# Power.net
KiCad netlist of a schematic drawn in Altium Designer
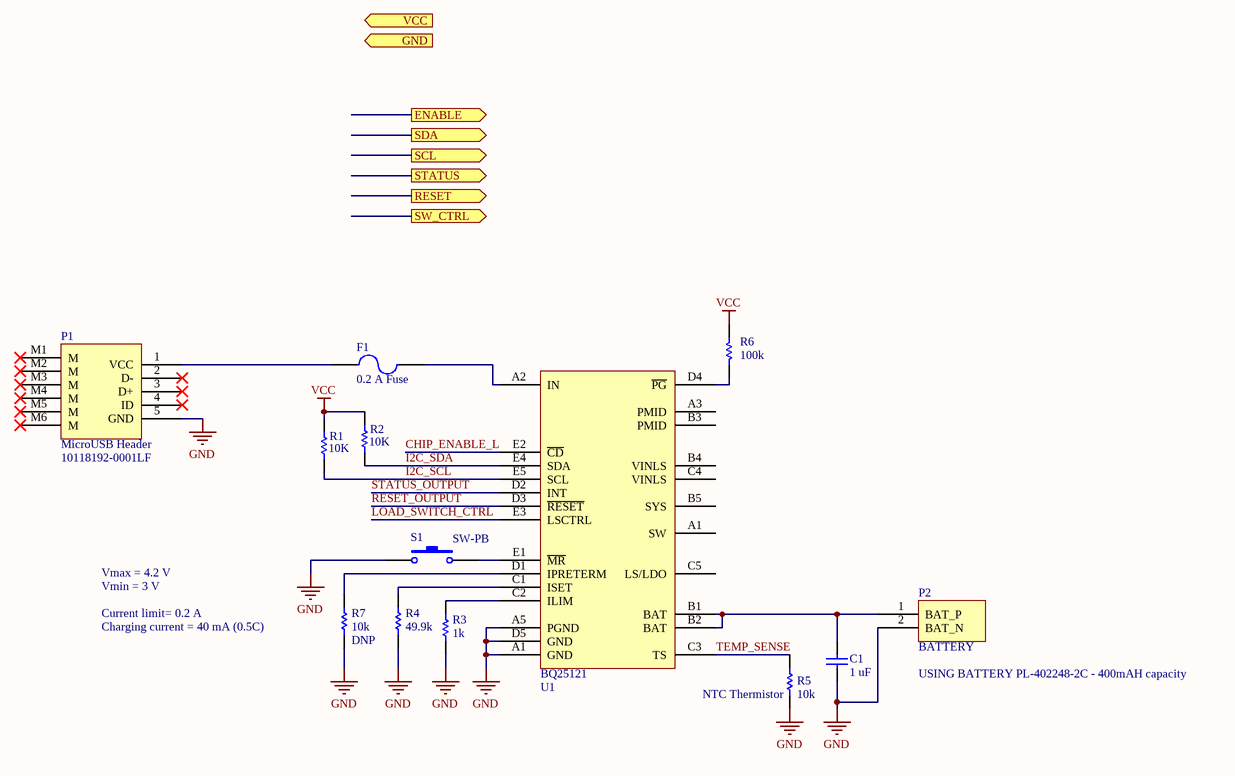
[diagram p0: Power.SchDoc]

(export (version "E")
  (design (tool "Eeschema 10.0.6"))
  (components
    (comp (ref "C1")
      (value "1 uF")
      (footprint "1608[0603]")
      (description "Capacitor")
      (fields (field (name "MANUFACTURER") "Murata") (field (name "Comment") "Cap"))
      (libsource (lib "Miscellaneous Devices") (part "Cap"))
    )
    (comp (ref "F1")
      (value "0.2 A Fuse")
      (footprint "Fuse_0603")
      (description "Fuse")
      (fields (field (name "MANUFACTURER") "AVX"))
      (libsource (lib "Miscellaneous Devices") (part "Fuse 2"))
    )
    (comp (ref "P1")
      (value "MicroUSB Header")
      (footprint "Micro USB B")
      (fields (field (name "MANUFACTURER") "Amphenol FCI") (field (name "MANUFACTURER PN") "10118192-0001LF"))
      (libsource (lib "Chirpwear") (part "Microusb"))
    )
    (comp (ref "P2") (value "BATTERY") (libsource (lib "Chirpwear") (part "BATTERY")))
    (comp (ref "R1")
      (value "10K")
      (footprint "RES0603")
      (description "Resistor")
      (fields (field (name "Comment") "Res1"))
      (libsource (lib "Miscellaneous Devices") (part "Res1"))
    )
    (comp (ref "R2")
      (value "10K")
      (footprint "RES0603")
      (description "Resistor")
      (fields (field (name "Comment") "Res1"))
      (libsource (lib "Miscellaneous Devices") (part "Res1"))
    )
    (comp (ref "R3")
      (value "1k")
      (footprint "RES0603")
      (description "Resistor")
      (fields (field (name "MANUFACTURER") "Yageo") (field (name "TOLERANCE") "1%"))
      (libsource (lib "Miscellaneous Devices") (part "Res1"))
    )
    (comp (ref "R4")
      (value "49.9k")
      (footprint "RES0603")
      (description "Resistor")
      (fields (field (name "MANUFACTURER") "Yageo") (field (name "TOLERANCE") "1%"))
      (libsource (lib "Miscellaneous Devices") (part "Res1"))
    )
    (comp (ref "R5")
      (value "10k")
      (footprint "AXIAL-0.3")
      (description "Resistor")
      (fields (field (name "Comment") "Res1"))
      (libsource (lib "Miscellaneous Devices") (part "Res1"))
    )
    (comp (ref "R6")
      (value "100k")
      (footprint "RES0603")
      (description "Resistor")
      (fields (field (name "MANUFACTURER") "Yageo") (field (name "TOLERANCE") "1%"))
      (libsource (lib "Miscellaneous Devices") (part "Res1"))
    )
    (comp (ref "R7")
      (value "10k")
      (footprint "AXIAL-0.3")
      (description "Resistor")
      (fields (field (name "NO_STUFF") "DNP") (field (name "Comment") "Res1"))
      (libsource (lib "Miscellaneous Devices") (part "Res1"))
    )
    (comp (ref "S1")
      (value "SW-PB")
      (footprint "SPST-2")
      (description "Switch")
      (fields (field (name "PUBLISHER") "Altium Limited"))
      (libsource (lib "Miscellaneous Devices") (part "SW-PB"))
    )
    (comp (ref "U1")
      (value "BQ25121")
      (description "IC BATT CHG LI-ION 25DSBGA")
      (fields (field (name "MANUFACTURER") "TI"))
      (libsource (lib "Chirpwear") (part "BQ2512X"))
    )
  )
  (nets
    (net (code "1") (name "/CHIP_ENABLE_L") (class "Default")
      (node (ref "U1") (pin "E2") (pinfunction "~{CD}_E2") (pintype "passive"))
    )
    (net (code "3") (name "/I2C_SCL") (class "Default")
      (node (ref "R1") (pin "1") (pinfunction "1_1") (pintype "passive"))
      (node (ref "U1") (pin "E5") (pinfunction "SCL_E5") (pintype "passive"))
    )
    (net (code "4") (name "/I2C_SDA") (class "Default")
      (node (ref "R2") (pin "1") (pinfunction "1_1") (pintype "passive"))
      (node (ref "U1") (pin "E4") (pinfunction "SDA_E4") (pintype "passive"))
    )
    (net (code "5") (name "/LOAD_SWITCH_CTRL") (class "Default")
      (node (ref "U1") (pin "E3") (pinfunction "LSCTRL_E3") (pintype "passive"))
    )
    (net (code "7") (name "/RESET_OUTPUT") (class "Default")
      (node (ref "U1") (pin "D3") (pinfunction "~{RESET}_D3") (pintype "passive"))
    )
    (net (code "11") (name "/STATUS_OUTPUT") (class "Default")
      (node (ref "U1") (pin "D2") (pinfunction "INT_D2") (pintype "passive"))
    )
    (net (code "13") (name "/TEMP_SENSE") (class "Default")
      (node (ref "R5") (pin "2") (pinfunction "2_2") (pintype "passive"))
      (node (ref "U1") (pin "C3") (pinfunction "TS_C3") (pintype "passive"))
    )
    (net (code "14") (name "GND") (class "Default")
      (node (ref "C1") (pin "1") (pinfunction "1_1") (pintype "passive"))
      (node (ref "P1") (pin "5") (pinfunction "GND_5") (pintype "passive"))
      (node (ref "P2") (pin "2") (pinfunction "BAT_N_2") (pintype "passive"))
      (node (ref "R3") (pin "1") (pinfunction "1_1") (pintype "passive"))
      (node (ref "R4") (pin "1") (pinfunction "1_1") (pintype "passive"))
      (node (ref "R5") (pin "1") (pinfunction "1_1") (pintype "passive"))
      (node (ref "R7") (pin "1") (pinfunction "1_1") (pintype "passive"))
      (node (ref "S1") (pin "1") (pinfunction "1_1") (pintype "passive"))
      (node (ref "U1") (pin "A1") (pinfunction "GND_A1") (pintype "passive"))
      (node (ref "U1") (pin "A5") (pinfunction "PGND_A5") (pintype "passive"))
      (node (ref "U1") (pin "D5") (pinfunction "GND_D5") (pintype "passive"))
    )
    (net (code "15") (name "Net-(P1-VCC)") (class "Default")
      (node (ref "F1") (pin "1") (pinfunction "1_1") (pintype "passive"))
      (node (ref "P1") (pin "1") (pinfunction "VCC_1") (pintype "passive"))
    )
    (net (code "16") (name "Net-(P2-BAT_P)") (class "Default")
      (node (ref "C1") (pin "2") (pinfunction "2_2") (pintype "passive"))
      (node (ref "P2") (pin "1") (pinfunction "BAT_P_1") (pintype "passive"))
      (node (ref "U1") (pin "B1") (pinfunction "BAT_B1") (pintype "passive"))
      (node (ref "U1") (pin "B2") (pinfunction "BAT_B2") (pintype "passive"))
    )
    (net (code "17") (name "Net-(U1-ILIM)") (class "Default")
      (node (ref "R3") (pin "2") (pinfunction "2_2") (pintype "passive"))
      (node (ref "U1") (pin "C2") (pinfunction "ILIM_C2") (pintype "passive"))
    )
    (net (code "18") (name "Net-(U1-IN)") (class "Default")
      (node (ref "F1") (pin "2") (pinfunction "2_2") (pintype "passive"))
      (node (ref "U1") (pin "A2") (pinfunction "IN_A2") (pintype "passive"))
    )
    (net (code "19") (name "Net-(U1-IPRETERM)") (class "Default")
      (node (ref "R7") (pin "2") (pinfunction "2_2") (pintype "passive"))
      (node (ref "U1") (pin "D1") (pinfunction "IPRETERM_D1") (pintype "passive"))
    )
    (net (code "20") (name "Net-(U1-ISET)") (class "Default")
      (node (ref "R4") (pin "2") (pinfunction "2_2") (pintype "passive"))
      (node (ref "U1") (pin "C1") (pinfunction "ISET_C1") (pintype "passive"))
    )
    (net (code "21") (name "Net-(U1-~{MR})") (class "Default")
      (node (ref "S1") (pin "2") (pinfunction "2_2") (pintype "passive"))
      (node (ref "U1") (pin "E1") (pinfunction "~{MR}_E1") (pintype "passive"))
    )
    (net (code "22") (name "Net-(U1-~{PG})") (class "Default")
      (node (ref "R6") (pin "1") (pinfunction "1_1") (pintype "passive"))
      (node (ref "U1") (pin "D4") (pinfunction "~{PG}_D4") (pintype "passive"))
    )
    (net (code "23") (name "VCC") (class "Default")
      (node (ref "R1") (pin "2") (pinfunction "2_2") (pintype "passive"))
      (node (ref "R2") (pin "2") (pinfunction "2_2") (pintype "passive"))
      (node (ref "R6") (pin "2") (pinfunction "2_2") (pintype "passive"))
    )
    (net (code "24") (name "unconnected-(P1-D+-Pad3)") (class "Default")
      (node (ref "P1") (pin "3") (pinfunction "D+_3") (pintype "passive+no_connect"))
    )
    (net (code "25") (name "unconnected-(P1-D--Pad2)") (class "Default")
      (node (ref "P1") (pin "2") (pinfunction "D-_2") (pintype "passive+no_connect"))
    )
    (net (code "26") (name "unconnected-(P1-ID-Pad4)") (class "Default")
      (node (ref "P1") (pin "4") (pinfunction "ID_4") (pintype "passive+no_connect"))
    )
    (net (code "27") (name "unconnected-(P1-M-PadM1)") (class "Default")
      (node (ref "P1") (pin "M1") (pinfunction "M_M1") (pintype "passive+no_connect"))
    )
    (net (code "28") (name "unconnected-(P1-M-PadM2)") (class "Default")
      (node (ref "P1") (pin "M2") (pinfunction "M_M2") (pintype "passive+no_connect"))
    )
    (net (code "29") (name "unconnected-(P1-M-PadM3)") (class "Default")
      (node (ref "P1") (pin "M3") (pinfunction "M_M3") (pintype "passive+no_connect"))
    )
    (net (code "30") (name "unconnected-(P1-M-PadM4)") (class "Default")
      (node (ref "P1") (pin "M4") (pinfunction "M_M4") (pintype "passive+no_connect"))
    )
    (net (code "31") (name "unconnected-(P1-M-PadM5)") (class "Default")
      (node (ref "P1") (pin "M5") (pinfunction "M_M5") (pintype "passive+no_connect"))
    )
    (net (code "32") (name "unconnected-(P1-M-PadM6)") (class "Default")
      (node (ref "P1") (pin "M6") (pinfunction "M_M6") (pintype "passive+no_connect"))
    )
    (net (code "33") (name "unconnected-(U1-LS{slash}LDO-PadC5)") (class "Default")
      (node (ref "U1") (pin "C5") (pinfunction "LS/LDO_C5") (pintype "passive"))
    )
    (net (code "34") (name "unconnected-(U1-PMID-PadA3)") (class "Default")
      (node (ref "U1") (pin "A3") (pinfunction "PMID_A3") (pintype "passive"))
    )
    (net (code "35") (name "unconnected-(U1-PMID-PadB3)") (class "Default")
      (node (ref "U1") (pin "B3") (pinfunction "PMID_B3") (pintype "passive"))
    )
    (net (code "36") (name "unconnected-(U1-SW-PadA1)") (class "Default")
      (node (ref "U1") (pin "A1") (pinfunction "SW_A1") (pintype "passive"))
    )
    (net (code "37") (name "unconnected-(U1-SYS-PadB5)") (class "Default")
      (node (ref "U1") (pin "B5") (pinfunction "SYS_B5") (pintype "passive"))
    )
    (net (code "38") (name "unconnected-(U1-VINLS-PadB4)") (class "Default")
      (node (ref "U1") (pin "B4") (pinfunction "VINLS_B4") (pintype "passive"))
    )
    (net (code "39") (name "unconnected-(U1-VINLS-PadC4)") (class "Default")
      (node (ref "U1") (pin "C4") (pinfunction "VINLS_C4") (pintype "passive"))
    )
  )
)
